# Line.net
KiCad netlist of a schematic drawn in EAGLE
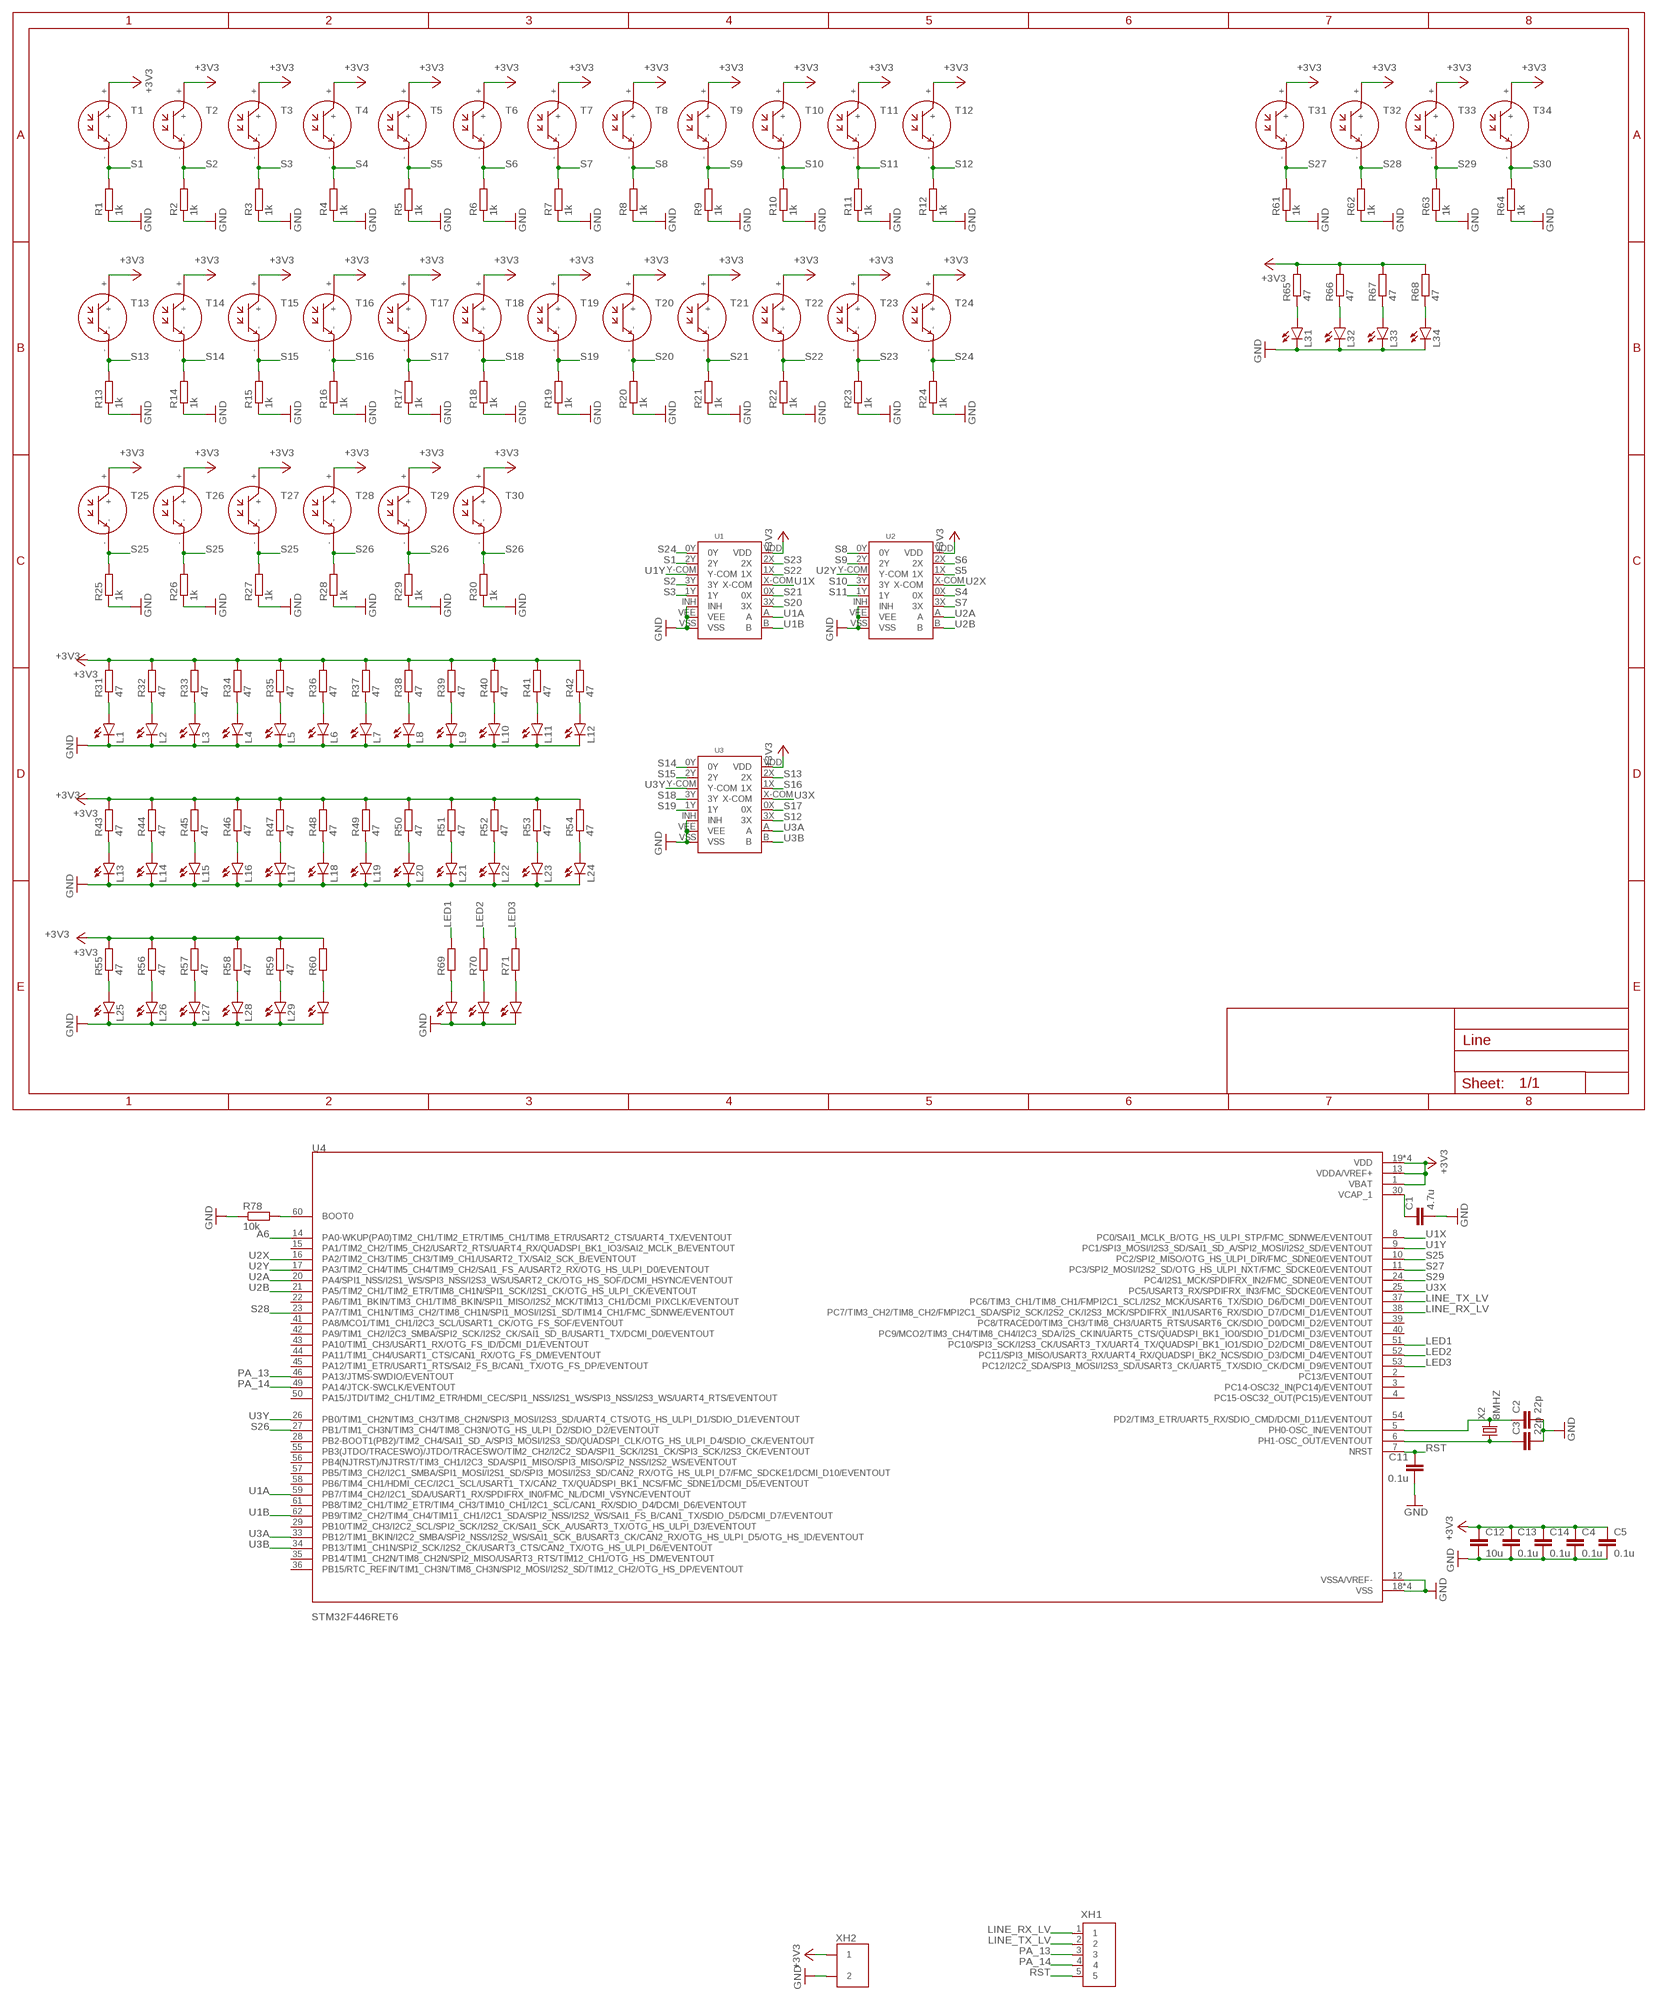
[diagram p0: schematic, sheet 1]

(export (version "E")
  (design (tool "Eeschema 10.0.6"))
  (components
    (comp (ref "C1")
      (value "4.7u")
      (footprint "eagle-import:C0603")
      (libsource (lib "eagle-import") (part "C-EUC0603"))
    )
    (comp (ref "C2")
      (value "22p")
      (footprint "eagle-import:C0603")
      (libsource (lib "eagle-import") (part "C-EUC0603"))
    )
    (comp (ref "C3")
      (value "22p")
      (footprint "eagle-import:C0603")
      (libsource (lib "eagle-import") (part "C-EUC0603"))
    )
    (comp (ref "C4")
      (value "0.1u")
      (footprint "eagle-import:C0603")
      (libsource (lib "eagle-import") (part "C-EUC0603"))
    )
    (comp (ref "C5")
      (value "0.1u")
      (footprint "eagle-import:C0603")
      (libsource (lib "eagle-import") (part "C-EUC0603"))
    )
    (comp (ref "C11")
      (value "0.1u")
      (footprint "eagle-import:C0603")
      (libsource (lib "eagle-import") (part "C-EUC0603"))
    )
    (comp (ref "C12")
      (value "10u")
      (footprint "eagle-import:C0805")
      (libsource (lib "eagle-import") (part "C-EUC0805"))
    )
    (comp (ref "C13")
      (value "0.1u")
      (footprint "eagle-import:C0603")
      (libsource (lib "eagle-import") (part "C-EUC0603"))
    )
    (comp (ref "C14")
      (value "0.1u")
      (footprint "eagle-import:C0603")
      (libsource (lib "eagle-import") (part "C-EUC0603"))
    )
    (comp (ref "L1")
      (value "SML-E12P8WT86")
      (footprint "eagle-import:LED_SML-LXFM0603SIC-TR")
      (libsource (lib "eagle-import") (part "SML-E12P8WT86"))
    )
    (comp (ref "L2")
      (value "SML-E12P8WT86")
      (footprint "eagle-import:LED_SML-LXFM0603SIC-TR")
      (libsource (lib "eagle-import") (part "SML-E12P8WT86"))
    )
    (comp (ref "L3")
      (value "SML-E12P8WT86")
      (footprint "eagle-import:LED_SML-LXFM0603SIC-TR")
      (libsource (lib "eagle-import") (part "SML-E12P8WT86"))
    )
    (comp (ref "L4")
      (value "SML-E12P8WT86")
      (footprint "eagle-import:LED_SML-LXFM0603SIC-TR")
      (libsource (lib "eagle-import") (part "SML-E12P8WT86"))
    )
    (comp (ref "L5")
      (value "SML-E12P8WT86")
      (footprint "eagle-import:LED_SML-LXFM0603SIC-TR")
      (libsource (lib "eagle-import") (part "SML-E12P8WT86"))
    )
    (comp (ref "L6")
      (value "SML-E12P8WT86")
      (footprint "eagle-import:LED_SML-LXFM0603SIC-TR")
      (libsource (lib "eagle-import") (part "SML-E12P8WT86"))
    )
    (comp (ref "L7")
      (value "SML-E12P8WT86")
      (footprint "eagle-import:LED_SML-LXFM0603SIC-TR")
      (libsource (lib "eagle-import") (part "SML-E12P8WT86"))
    )
    (comp (ref "L8")
      (value "SML-E12P8WT86")
      (footprint "eagle-import:LED_SML-LXFM0603SIC-TR")
      (libsource (lib "eagle-import") (part "SML-E12P8WT86"))
    )
    (comp (ref "L9")
      (value "SML-E12P8WT86")
      (footprint "eagle-import:LED_SML-LXFM0603SIC-TR")
      (libsource (lib "eagle-import") (part "SML-E12P8WT86"))
    )
    (comp (ref "L10")
      (value "SML-E12P8WT86")
      (footprint "eagle-import:LED_SML-LXFM0603SIC-TR")
      (libsource (lib "eagle-import") (part "SML-E12P8WT86"))
    )
    (comp (ref "L11")
      (value "SML-E12P8WT86")
      (footprint "eagle-import:LED_SML-LXFM0603SIC-TR")
      (libsource (lib "eagle-import") (part "SML-E12P8WT86"))
    )
    (comp (ref "L12")
      (value "SML-E12P8WT86")
      (footprint "eagle-import:LED_SML-LXFM0603SIC-TR")
      (libsource (lib "eagle-import") (part "SML-E12P8WT86"))
    )
    (comp (ref "L13")
      (value "SML-E12P8WT86")
      (footprint "eagle-import:LED_SML-LXFM0603SIC-TR")
      (libsource (lib "eagle-import") (part "SML-E12P8WT86"))
    )
    (comp (ref "L14")
      (value "SML-E12P8WT86")
      (footprint "eagle-import:LED_SML-LXFM0603SIC-TR")
      (libsource (lib "eagle-import") (part "SML-E12P8WT86"))
    )
    (comp (ref "L15")
      (value "SML-E12P8WT86")
      (footprint "eagle-import:LED_SML-LXFM0603SIC-TR")
      (libsource (lib "eagle-import") (part "SML-E12P8WT86"))
    )
    (comp (ref "L16")
      (value "SML-E12P8WT86")
      (footprint "eagle-import:LED_SML-LXFM0603SIC-TR")
      (libsource (lib "eagle-import") (part "SML-E12P8WT86"))
    )
    (comp (ref "L17")
      (value "SML-E12P8WT86")
      (footprint "eagle-import:LED_SML-LXFM0603SIC-TR")
      (libsource (lib "eagle-import") (part "SML-E12P8WT86"))
    )
    (comp (ref "L18")
      (value "SML-E12P8WT86")
      (footprint "eagle-import:LED_SML-LXFM0603SIC-TR")
      (libsource (lib "eagle-import") (part "SML-E12P8WT86"))
    )
    (comp (ref "L19")
      (value "SML-E12P8WT86")
      (footprint "eagle-import:LED_SML-LXFM0603SIC-TR")
      (libsource (lib "eagle-import") (part "SML-E12P8WT86"))
    )
    (comp (ref "L20")
      (value "SML-E12P8WT86")
      (footprint "eagle-import:LED_SML-LXFM0603SIC-TR")
      (libsource (lib "eagle-import") (part "SML-E12P8WT86"))
    )
    (comp (ref "L21")
      (value "SML-E12P8WT86")
      (footprint "eagle-import:LED_SML-LXFM0603SIC-TR")
      (libsource (lib "eagle-import") (part "SML-E12P8WT86"))
    )
    (comp (ref "L22")
      (value "SML-E12P8WT86")
      (footprint "eagle-import:LED_SML-LXFM0603SIC-TR")
      (libsource (lib "eagle-import") (part "SML-E12P8WT86"))
    )
    (comp (ref "L23")
      (value "SML-E12P8WT86")
      (footprint "eagle-import:LED_SML-LXFM0603SIC-TR")
      (libsource (lib "eagle-import") (part "SML-E12P8WT86"))
    )
    (comp (ref "L24")
      (value "SML-E12P8WT86")
      (footprint "eagle-import:LED_SML-LXFM0603SIC-TR")
      (libsource (lib "eagle-import") (part "SML-E12P8WT86"))
    )
    (comp (ref "L25")
      (value "SML-E12P8WT86")
      (footprint "eagle-import:LED_SML-LXFM0603SIC-TR")
      (libsource (lib "eagle-import") (part "SML-E12P8WT86"))
    )
    (comp (ref "L26")
      (value "SML-E12P8WT86")
      (footprint "eagle-import:LED_SML-LXFM0603SIC-TR")
      (libsource (lib "eagle-import") (part "SML-E12P8WT86"))
    )
    (comp (ref "L27")
      (value "SML-E12P8WT86")
      (footprint "eagle-import:LED_SML-LXFM0603SIC-TR")
      (libsource (lib "eagle-import") (part "SML-E12P8WT86"))
    )
    (comp (ref "L28")
      (value "SML-E12P8WT86")
      (footprint "eagle-import:LED_SML-LXFM0603SIC-TR")
      (libsource (lib "eagle-import") (part "SML-E12P8WT86"))
    )
    (comp (ref "L29")
      (value "SML-E12P8WT86")
      (footprint "eagle-import:LED_SML-LXFM0603SIC-TR")
      (libsource (lib "eagle-import") (part "SML-E12P8WT86"))
    )
    (comp (ref "L30")
      (value "SML-E12P8WT86")
      (footprint "eagle-import:LED_SML-LXFM0603SIC-TR")
      (libsource (lib "eagle-import") (part "SML-E12P8WT86"))
    )
    (comp (ref "L31")
      (value "SML-E12P8WT86")
      (footprint "eagle-import:LED_SML-LXFM0603SIC-TR")
      (libsource (lib "eagle-import") (part "SML-E12P8WT86"))
    )
    (comp (ref "L32")
      (value "SML-E12P8WT86")
      (footprint "eagle-import:LED_SML-LXFM0603SIC-TR")
      (libsource (lib "eagle-import") (part "SML-E12P8WT86"))
    )
    (comp (ref "L33")
      (value "SML-E12P8WT86")
      (footprint "eagle-import:LED_SML-LXFM0603SIC-TR")
      (libsource (lib "eagle-import") (part "SML-E12P8WT86"))
    )
    (comp (ref "L34")
      (value "SML-E12P8WT86")
      (footprint "eagle-import:LED_SML-LXFM0603SIC-TR")
      (libsource (lib "eagle-import") (part "SML-E12P8WT86"))
    )
    (comp (ref "L35")
      (value "SML-E12P8WT86")
      (footprint "eagle-import:LED_SML-LXFM0603SIC-TR")
      (libsource (lib "eagle-import") (part "SML-E12P8WT86"))
    )
    (comp (ref "L36")
      (value "SML-E12P8WT86")
      (footprint "eagle-import:LED_SML-LXFM0603SIC-TR")
      (libsource (lib "eagle-import") (part "SML-E12P8WT86"))
    )
    (comp (ref "L37")
      (value "SML-E12P8WT86")
      (footprint "eagle-import:LED_SML-LXFM0603SIC-TR")
      (libsource (lib "eagle-import") (part "SML-E12P8WT86"))
    )
    (comp (ref "R1")
      (value "1k")
      (footprint "eagle-import:R0603")
      (libsource (lib "eagle-import") (part "R-EU_R0603"))
    )
    (comp (ref "R2")
      (value "1k")
      (footprint "eagle-import:R0603")
      (libsource (lib "eagle-import") (part "R-EU_R0603"))
    )
    (comp (ref "R3")
      (value "1k")
      (footprint "eagle-import:R0603")
      (libsource (lib "eagle-import") (part "R-EU_R0603"))
    )
    (comp (ref "R4")
      (value "1k")
      (footprint "eagle-import:R0603")
      (libsource (lib "eagle-import") (part "R-EU_R0603"))
    )
    (comp (ref "R5")
      (value "1k")
      (footprint "eagle-import:R0603")
      (libsource (lib "eagle-import") (part "R-EU_R0603"))
    )
    (comp (ref "R6")
      (value "1k")
      (footprint "eagle-import:R0603")
      (libsource (lib "eagle-import") (part "R-EU_R0603"))
    )
    (comp (ref "R7")
      (value "1k")
      (footprint "eagle-import:R0603")
      (libsource (lib "eagle-import") (part "R-EU_R0603"))
    )
    (comp (ref "R8")
      (value "1k")
      (footprint "eagle-import:R0603")
      (libsource (lib "eagle-import") (part "R-EU_R0603"))
    )
    (comp (ref "R9")
      (value "1k")
      (footprint "eagle-import:R0603")
      (libsource (lib "eagle-import") (part "R-EU_R0603"))
    )
    (comp (ref "R10")
      (value "1k")
      (footprint "eagle-import:R0603")
      (libsource (lib "eagle-import") (part "R-EU_R0603"))
    )
    (comp (ref "R11")
      (value "1k")
      (footprint "eagle-import:R0603")
      (libsource (lib "eagle-import") (part "R-EU_R0603"))
    )
    (comp (ref "R12")
      (value "1k")
      (footprint "eagle-import:R0603")
      (libsource (lib "eagle-import") (part "R-EU_R0603"))
    )
    (comp (ref "R13")
      (value "1k")
      (footprint "eagle-import:R0603")
      (libsource (lib "eagle-import") (part "R-EU_R0603"))
    )
    (comp (ref "R14")
      (value "1k")
      (footprint "eagle-import:R0603")
      (libsource (lib "eagle-import") (part "R-EU_R0603"))
    )
    (comp (ref "R15")
      (value "1k")
      (footprint "eagle-import:R0603")
      (libsource (lib "eagle-import") (part "R-EU_R0603"))
    )
    (comp (ref "R16")
      (value "1k")
      (footprint "eagle-import:R0603")
      (libsource (lib "eagle-import") (part "R-EU_R0603"))
    )
    (comp (ref "R17")
      (value "1k")
      (footprint "eagle-import:R0603")
      (libsource (lib "eagle-import") (part "R-EU_R0603"))
    )
    (comp (ref "R18")
      (value "1k")
      (footprint "eagle-import:R0603")
      (libsource (lib "eagle-import") (part "R-EU_R0603"))
    )
    (comp (ref "R19")
      (value "1k")
      (footprint "eagle-import:R0603")
      (libsource (lib "eagle-import") (part "R-EU_R0603"))
    )
    (comp (ref "R20")
      (value "1k")
      (footprint "eagle-import:R0603")
      (libsource (lib "eagle-import") (part "R-EU_R0603"))
    )
    (comp (ref "R21")
      (value "1k")
      (footprint "eagle-import:R0603")
      (libsource (lib "eagle-import") (part "R-EU_R0603"))
    )
    (comp (ref "R22")
      (value "1k")
      (footprint "eagle-import:R0603")
      (libsource (lib "eagle-import") (part "R-EU_R0603"))
    )
    (comp (ref "R23")
      (value "1k")
      (footprint "eagle-import:R0603")
      (libsource (lib "eagle-import") (part "R-EU_R0603"))
    )
    (comp (ref "R24")
      (value "1k")
      (footprint "eagle-import:R0603")
      (libsource (lib "eagle-import") (part "R-EU_R0603"))
    )
    (comp (ref "R25")
      (value "1k")
      (footprint "eagle-import:R0603")
      (libsource (lib "eagle-import") (part "R-EU_R0603"))
    )
    (comp (ref "R26")
      (value "1k")
      (footprint "eagle-import:R0603")
      (libsource (lib "eagle-import") (part "R-EU_R0603"))
    )
    (comp (ref "R27")
      (value "1k")
      (footprint "eagle-import:R0603")
      (libsource (lib "eagle-import") (part "R-EU_R0603"))
    )
    (comp (ref "R28")
      (value "1k")
      (footprint "eagle-import:R0603")
      (libsource (lib "eagle-import") (part "R-EU_R0603"))
    )
    (comp (ref "R29")
      (value "1k")
      (footprint "eagle-import:R0603")
      (libsource (lib "eagle-import") (part "R-EU_R0603"))
    )
    (comp (ref "R30")
      (value "1k")
      (footprint "eagle-import:R0603")
      (libsource (lib "eagle-import") (part "R-EU_R0603"))
    )
    (comp (ref "R31")
      (value "47")
      (footprint "eagle-import:R0603")
      (libsource (lib "eagle-import") (part "R-EU_R0603"))
    )
    (comp (ref "R32")
      (value "47")
      (footprint "eagle-import:R0603")
      (libsource (lib "eagle-import") (part "R-EU_R0603"))
    )
    (comp (ref "R33")
      (value "47")
      (footprint "eagle-import:R0603")
      (libsource (lib "eagle-import") (part "R-EU_R0603"))
    )
    (comp (ref "R34")
      (value "47")
      (footprint "eagle-import:R0603")
      (libsource (lib "eagle-import") (part "R-EU_R0603"))
    )
    (comp (ref "R35")
      (value "47")
      (footprint "eagle-import:R0603")
      (libsource (lib "eagle-import") (part "R-EU_R0603"))
    )
    (comp (ref "R36")
      (value "47")
      (footprint "eagle-import:R0603")
      (libsource (lib "eagle-import") (part "R-EU_R0603"))
    )
    (comp (ref "R37")
      (value "47")
      (footprint "eagle-import:R0603")
      (libsource (lib "eagle-import") (part "R-EU_R0603"))
    )
    (comp (ref "R38")
      (value "47")
      (footprint "eagle-import:R0603")
      (libsource (lib "eagle-import") (part "R-EU_R0603"))
    )
    (comp (ref "R39")
      (value "47")
      (footprint "eagle-import:R0603")
      (libsource (lib "eagle-import") (part "R-EU_R0603"))
    )
    (comp (ref "R40")
      (value "47")
      (footprint "eagle-import:R0603")
      (libsource (lib "eagle-import") (part "R-EU_R0603"))
    )
    (comp (ref "R41")
      (value "47")
      (footprint "eagle-import:R0603")
      (libsource (lib "eagle-import") (part "R-EU_R0603"))
    )
    (comp (ref "R42")
      (value "47")
      (footprint "eagle-import:R0603")
      (libsource (lib "eagle-import") (part "R-EU_R0603"))
    )
    (comp (ref "R43")
      (value "47")
      (footprint "eagle-import:R0603")
      (libsource (lib "eagle-import") (part "R-EU_R0603"))
    )
    (comp (ref "R44")
      (value "47")
      (footprint "eagle-import:R0603")
      (libsource (lib "eagle-import") (part "R-EU_R0603"))
    )
    (comp (ref "R45")
      (value "47")
      (footprint "eagle-import:R0603")
      (libsource (lib "eagle-import") (part "R-EU_R0603"))
    )
    (comp (ref "R46")
      (value "47")
      (footprint "eagle-import:R0603")
      (libsource (lib "eagle-import") (part "R-EU_R0603"))
    )
    (comp (ref "R47")
      (value "47")
      (footprint "eagle-import:R0603")
      (libsource (lib "eagle-import") (part "R-EU_R0603"))
    )
    (comp (ref "R48")
      (value "47")
      (footprint "eagle-import:R0603")
      (libsource (lib "eagle-import") (part "R-EU_R0603"))
    )
    (comp (ref "R49")
      (value "47")
      (footprint "eagle-import:R0603")
      (libsource (lib "eagle-import") (part "R-EU_R0603"))
    )
    (comp (ref "R50")
      (value "47")
      (footprint "eagle-import:R0603")
      (libsource (lib "eagle-import") (part "R-EU_R0603"))
    )
    (comp (ref "R51")
      (value "47")
      (footprint "eagle-import:R0603")
      (libsource (lib "eagle-import") (part "R-EU_R0603"))
    )
    (comp (ref "R52")
      (value "47")
      (footprint "eagle-import:R0603")
      (libsource (lib "eagle-import") (part "R-EU_R0603"))
    )
    (comp (ref "R53")
      (value "47")
      (footprint "eagle-import:R0603")
      (libsource (lib "eagle-import") (part "R-EU_R0603"))
    )
    (comp (ref "R54")
      (value "47")
      (footprint "eagle-import:R0603")
      (libsource (lib "eagle-import") (part "R-EU_R0603"))
    )
    (comp (ref "R55")
      (value "47")
      (footprint "eagle-import:R0603")
      (libsource (lib "eagle-import") (part "R-EU_R0603"))
    )
    (comp (ref "R56")
      (value "47")
      (footprint "eagle-import:R0603")
      (libsource (lib "eagle-import") (part "R-EU_R0603"))
    )
    (comp (ref "R57")
      (value "47")
      (footprint "eagle-import:R0603")
      (libsource (lib "eagle-import") (part "R-EU_R0603"))
    )
    (comp (ref "R58")
      (value "47")
      (footprint "eagle-import:R0603")
      (libsource (lib "eagle-import") (part "R-EU_R0603"))
    )
    (comp (ref "R59")
      (value "47")
      (footprint "eagle-import:R0603")
      (libsource (lib "eagle-import") (part "R-EU_R0603"))
    )
    (comp (ref "R60")
      (value "47")
      (footprint "eagle-import:R0603")
      (libsource (lib "eagle-import") (part "R-EU_R0603"))
    )
    (comp (ref "R61")
      (value "1k")
      (footprint "eagle-import:R0603")
      (libsource (lib "eagle-import") (part "R-EU_R0603"))
    )
    (comp (ref "R62")
      (value "1k")
      (footprint "eagle-import:R0603")
      (libsource (lib "eagle-import") (part "R-EU_R0603"))
    )
    (comp (ref "R63")
      (value "1k")
      (footprint "eagle-import:R0603")
      (libsource (lib "eagle-import") (part "R-EU_R0603"))
    )
    (comp (ref "R64")
      (value "1k")
      (footprint "eagle-import:R0603")
      (libsource (lib "eagle-import") (part "R-EU_R0603"))
    )
    (comp (ref "R65")
      (value "47")
      (footprint "eagle-import:R0603")
      (libsource (lib "eagle-import") (part "R-EU_R0603"))
    )
    (comp (ref "R66")
      (value "47")
      (footprint "eagle-import:R0603")
      (libsource (lib "eagle-import") (part "R-EU_R0603"))
    )
    (comp (ref "R67")
      (value "47")
      (footprint "eagle-import:R0603")
      (libsource (lib "eagle-import") (part "R-EU_R0603"))
    )
    (comp (ref "R68")
      (value "47")
      (footprint "eagle-import:R0603")
      (libsource (lib "eagle-import") (part "R-EU_R0603"))
    )
    (comp (ref "R69")
      (value "150")
      (footprint "eagle-import:R0603")
      (libsource (lib "eagle-import") (part "R-EU_R0603"))
    )
    (comp (ref "R70")
      (value "150")
      (footprint "eagle-import:R0603")
      (libsource (lib "eagle-import") (part "R-EU_R0603"))
    )
    (comp (ref "R71")
      (value "150")
      (footprint "eagle-import:R0603")
      (libsource (lib "eagle-import") (part "R-EU_R0603"))
    )
    (comp (ref "R78")
      (value "10k")
      (footprint "eagle-import:R0603")
      (libsource (lib "eagle-import") (part "R-EU_R0603"))
    )
    (comp (ref "T1")
      (value "NJL7302L-F3")
      (footprint "eagle-import:NJL7302L-F3")
      (libsource (lib "eagle-import") (part "NJL7302L-F3"))
    )
    (comp (ref "T2")
      (value "NJL7302L-F3")
      (footprint "eagle-import:NJL7302L-F3")
      (libsource (lib "eagle-import") (part "NJL7302L-F3"))
    )
    (comp (ref "T3")
      (value "NJL7302L-F3")
      (footprint "eagle-import:NJL7302L-F3")
      (libsource (lib "eagle-import") (part "NJL7302L-F3"))
    )
    (comp (ref "T4")
      (value "NJL7302L-F3")
      (footprint "eagle-import:NJL7302L-F3")
      (libsource (lib "eagle-import") (part "NJL7302L-F3"))
    )
    (comp (ref "T5")
      (value "NJL7302L-F3")
      (footprint "eagle-import:NJL7302L-F3")
      (libsource (lib "eagle-import") (part "NJL7302L-F3"))
    )
    (comp (ref "T6")
      (value "NJL7302L-F3")
      (footprint "eagle-import:NJL7302L-F3")
      (libsource (lib "eagle-import") (part "NJL7302L-F3"))
    )
    (comp (ref "T7")
      (value "NJL7302L-F3")
      (footprint "eagle-import:NJL7302L-F3")
      (libsource (lib "eagle-import") (part "NJL7302L-F3"))
    )
    (comp (ref "T8")
      (value "NJL7302L-F3")
      (footprint "eagle-import:NJL7302L-F3")
      (libsource (lib "eagle-import") (part "NJL7302L-F3"))
    )
    (comp (ref "T9")
      (value "NJL7302L-F3")
      (footprint "eagle-import:NJL7302L-F3")
      (libsource (lib "eagle-import") (part "NJL7302L-F3"))
    )
    (comp (ref "T10")
      (value "NJL7302L-F3")
      (footprint "eagle-import:NJL7302L-F3")
      (libsource (lib "eagle-import") (part "NJL7302L-F3"))
    )
    (comp (ref "T11")
      (value "NJL7302L-F3")
      (footprint "eagle-import:NJL7302L-F3")
      (libsource (lib "eagle-import") (part "NJL7302L-F3"))
    )
    (comp (ref "T12")
      (value "NJL7302L-F3")
      (footprint "eagle-import:NJL7302L-F3")
      (libsource (lib "eagle-import") (part "NJL7302L-F3"))
    )
    (comp (ref "T13")
      (value "NJL7302L-F3")
      (footprint "eagle-import:NJL7302L-F3")
      (libsource (lib "eagle-import") (part "NJL7302L-F3"))
    )
    (comp (ref "T14")
      (value "NJL7302L-F3")
      (footprint "eagle-import:NJL7302L-F3")
      (libsource (lib "eagle-import") (part "NJL7302L-F3"))
    )
    (comp (ref "T15")
      (value "NJL7302L-F3")
      (footprint "eagle-import:NJL7302L-F3")
      (libsource (lib "eagle-import") (part "NJL7302L-F3"))
    )
    (comp (ref "T16")
      (value "NJL7302L-F3")
      (footprint "eagle-import:NJL7302L-F3")
      (libsource (lib "eagle-import") (part "NJL7302L-F3"))
    )
    (comp (ref "T17")
      (value "NJL7302L-F3")
      (footprint "eagle-import:NJL7302L-F3")
      (libsource (lib "eagle-import") (part "NJL7302L-F3"))
    )
    (comp (ref "T18")
      (value "NJL7302L-F3")
      (footprint "eagle-import:NJL7302L-F3")
      (libsource (lib "eagle-import") (part "NJL7302L-F3"))
    )
    (comp (ref "T19")
      (value "NJL7302L-F3")
      (footprint "eagle-import:NJL7302L-F3")
      (libsource (lib "eagle-import") (part "NJL7302L-F3"))
    )
    (comp (ref "T20")
      (value "NJL7302L-F3")
      (footprint "eagle-import:NJL7302L-F3")
      (libsource (lib "eagle-import") (part "NJL7302L-F3"))
    )
    (comp (ref "T21")
      (value "NJL7302L-F3")
      (footprint "eagle-import:NJL7302L-F3")
      (libsource (lib "eagle-import") (part "NJL7302L-F3"))
    )
    (comp (ref "T22")
      (value "NJL7302L-F3")
      (footprint "eagle-import:NJL7302L-F3")
      (libsource (lib "eagle-import") (part "NJL7302L-F3"))
    )
    (comp (ref "T23")
      (value "NJL7302L-F3")
      (footprint "eagle-import:NJL7302L-F3")
      (libsource (lib "eagle-import") (part "NJL7302L-F3"))
    )
    (comp (ref "T24")
      (value "NJL7302L-F3")
      (footprint "eagle-import:NJL7302L-F3")
      (libsource (lib "eagle-import") (part "NJL7302L-F3"))
    )
    (comp (ref "T25")
      (value "NJL7302L-F3")
      (footprint "eagle-import:NJL7302L-F3")
      (libsource (lib "eagle-import") (part "NJL7302L-F3"))
    )
    (comp (ref "T26")
      (value "NJL7302L-F3")
      (footprint "eagle-import:NJL7302L-F3")
      (libsource (lib "eagle-import") (part "NJL7302L-F3"))
    )
    (comp (ref "T27")
      (value "NJL7302L-F3")
      (footprint "eagle-import:NJL7302L-F3")
      (libsource (lib "eagle-import") (part "NJL7302L-F3"))
    )
    (comp (ref "T28")
      (value "NJL7302L-F3")
      (footprint "eagle-import:NJL7302L-F3")
      (libsource (lib "eagle-import") (part "NJL7302L-F3"))
    )
    (comp (ref "T29")
      (value "NJL7302L-F3")
      (footprint "eagle-import:NJL7302L-F3")
      (libsource (lib "eagle-import") (part "NJL7302L-F3"))
    )
    (comp (ref "T30")
      (value "NJL7302L-F3")
      (footprint "eagle-import:NJL7302L-F3")
      (libsource (lib "eagle-import") (part "NJL7302L-F3"))
    )
    (comp (ref "T31")
      (value "NJL7302L-F3")
      (footprint "eagle-import:NJL7302L-F3")
      (libsource (lib "eagle-import") (part "NJL7302L-F3"))
    )
    (comp (ref "T32")
      (value "NJL7302L-F3")
      (footprint "eagle-import:NJL7302L-F3")
      (libsource (lib "eagle-import") (part "NJL7302L-F3"))
    )
    (comp (ref "T33")
      (value "NJL7302L-F3")
      (footprint "eagle-import:NJL7302L-F3")
      (libsource (lib "eagle-import") (part "NJL7302L-F3"))
    )
    (comp (ref "T34")
      (value "NJL7302L-F3")
      (footprint "eagle-import:NJL7302L-F3")
      (libsource (lib "eagle-import") (part "NJL7302L-F3"))
    )
    (comp (ref "U1")
      (value "TC4051BP")
      (footprint "eagle-import:TC4051BP")
      (libsource (lib "eagle-import") (part "TC4051BP"))
    )
    (comp (ref "U2")
      (value "TC4051BP")
      (footprint "eagle-import:TC4051BP")
      (libsource (lib "eagle-import") (part "TC4051BP"))
    )
    (comp (ref "U3")
      (value "TC4051BP")
      (footprint "eagle-import:TC4051BP")
      (libsource (lib "eagle-import") (part "TC4051BP"))
    )
    (comp (ref "U4")
      (value "STM32F446RET6")
      (footprint "eagle-import:QFP50P1200X1200X160-64N")
      (fields (field (name "MF") "STMicroelectronics"))
      (libsource (lib "eagle-import") (part "STM32F446RET6"))
    )
    (comp (ref "X2")
      (value "8MHZ")
      (footprint "eagle-import:16MHZ")
      (libsource (lib "eagle-import") (part "16MHZ"))
    )
    (comp (ref "XH1") (value "5B") (footprint "eagle-import:5B") (libsource (lib "eagle-import") (part "5B")))
    (comp (ref "XH2") (value "2B") (footprint "eagle-import:2B") (libsource (lib "eagle-import") (part "2B")))
  )
  (nets
    (net (code "1") (name "+3V3") (class "Default")
      (node (ref "C12") (pin "1") (pinfunction "1_1") (pintype "passive"))
      (node (ref "C13") (pin "1") (pinfunction "1_1") (pintype "passive"))
      (node (ref "C14") (pin "1") (pinfunction "1_1") (pintype "passive"))
      (node (ref "C4") (pin "1") (pinfunction "1_1") (pintype "passive"))
      (node (ref "C5") (pin "1") (pinfunction "1_1") (pintype "passive"))
      (node (ref "R31") (pin "2") (pinfunction "2_2") (pintype "passive"))
      (node (ref "R32") (pin "2") (pinfunction "2_2") (pintype "passive"))
      (node (ref "R33") (pin "2") (pinfunction "2_2") (pintype "passive"))
      (node (ref "R34") (pin "2") (pinfunction "2_2") (pintype "passive"))
      (node (ref "R35") (pin "2") (pinfunction "2_2") (pintype "passive"))
      (node (ref "R36") (pin "2") (pinfunction "2_2") (pintype "passive"))
      (node (ref "R37") (pin "2") (pinfunction "2_2") (pintype "passive"))
      (node (ref "R38") (pin "2") (pinfunction "2_2") (pintype "passive"))
      (node (ref "R39") (pin "2") (pinfunction "2_2") (pintype "passive"))
      (node (ref "R40") (pin "2") (pinfunction "2_2") (pintype "passive"))
      (node (ref "R41") (pin "2") (pinfunction "2_2") (pintype "passive"))
      (node (ref "R42") (pin "2") (pinfunction "2_2") (pintype "passive"))
      (node (ref "R43") (pin "2") (pinfunction "2_2") (pintype "passive"))
      (node (ref "R44") (pin "2") (pinfunction "2_2") (pintype "passive"))
      (node (ref "R45") (pin "2") (pinfunction "2_2") (pintype "passive"))
      (node (ref "R46") (pin "2") (pinfunction "2_2") (pintype "passive"))
      (node (ref "R47") (pin "2") (pinfunction "2_2") (pintype "passive"))
      (node (ref "R48") (pin "2") (pinfunction "2_2") (pintype "passive"))
      (node (ref "R49") (pin "2") (pinfunction "2_2") (pintype "passive"))
      (node (ref "R50") (pin "2") (pinfunction "2_2") (pintype "passive"))
      (node (ref "R51") (pin "2") (pinfunction "2_2") (pintype "passive"))
      (node (ref "R52") (pin "2") (pinfunction "2_2") (pintype "passive"))
      (node (ref "R53") (pin "2") (pinfunction "2_2") (pintype "passive"))
      (node (ref "R54") (pin "2") (pinfunction "2_2") (pintype "passive"))
      (node (ref "R55") (pin "2") (pinfunction "2_2") (pintype "passive"))
      (node (ref "R56") (pin "2") (pinfunction "2_2") (pintype "passive"))
      (node (ref "R57") (pin "2") (pinfunction "2_2") (pintype "passive"))
      (node (ref "R58") (pin "2") (pinfunction "2_2") (pintype "passive"))
      (node (ref "R59") (pin "2") (pinfunction "2_2") (pintype "passive"))
      (node (ref "R60") (pin "2") (pinfunction "2_2") (pintype "passive"))
      (node (ref "R65") (pin "2") (pinfunction "2_2") (pintype "passive"))
      (node (ref "R66") (pin "2") (pinfunction "2_2") (pintype "passive"))
      (node (ref "R67") (pin "2") (pinfunction "2_2") (pintype "passive"))
      (node (ref "R68") (pin "2") (pinfunction "2_2") (pintype "passive"))
      (node (ref "T1") (pin "+") (pinfunction "+_+") (pintype "bidirectional"))
      (node (ref "T10") (pin "+") (pinfunction "+_+") (pintype "bidirectional"))
      (node (ref "T11") (pin "+") (pinfunction "+_+") (pintype "bidirectional"))
      (node (ref "T12") (pin "+") (pinfunction "+_+") (pintype "bidirectional"))
      (node (ref "T13") (pin "+") (pinfunction "+_+") (pintype "bidirectional"))
      (node (ref "T14") (pin "+") (pinfunction "+_+") (pintype "bidirectional"))
      (node (ref "T15") (pin "+") (pinfunction "+_+") (pintype "bidirectional"))
      (node (ref "T16") (pin "+") (pinfunction "+_+") (pintype "bidirectional"))
      (node (ref "T17") (pin "+") (pinfunction "+_+") (pintype "bidirectional"))
      (node (ref "T18") (pin "+") (pinfunction "+_+") (pintype "bidirectional"))
      (node (ref "T19") (pin "+") (pinfunction "+_+") (pintype "bidirectional"))
      (node (ref "T2") (pin "+") (pinfunction "+_+") (pintype "bidirectional"))
      (node (ref "T20") (pin "+") (pinfunction "+_+") (pintype "bidirectional"))
      (node (ref "T21") (pin "+") (pinfunction "+_+") (pintype "bidirectional"))
      (node (ref "T22") (pin "+") (pinfunction "+_+") (pintype "bidirectional"))
      (node (ref "T23") (pin "+") (pinfunction "+_+") (pintype "bidirectional"))
      (node (ref "T24") (pin "+") (pinfunction "+_+") (pintype "bidirectional"))
      (node (ref "T25") (pin "+") (pinfunction "+_+") (pintype "bidirectional"))
      (node (ref "T26") (pin "+") (pinfunction "+_+") (pintype "bidirectional"))
      (node (ref "T27") (pin "+") (pinfunction "+_+") (pintype "bidirectional"))
      (node (ref "T28") (pin "+") (pinfunction "+_+") (pintype "bidirectional"))
      (node (ref "T29") (pin "+") (pinfunction "+_+") (pintype "bidirectional"))
      (node (ref "T3") (pin "+") (pinfunction "+_+") (pintype "bidirectional"))
      (node (ref "T30") (pin "+") (pinfunction "+_+") (pintype "bidirectional"))
      (node (ref "T31") (pin "+") (pinfunction "+_+") (pintype "bidirectional"))
      (node (ref "T32") (pin "+") (pinfunction "+_+") (pintype "bidirectional"))
      (node (ref "T33") (pin "+") (pinfunction "+_+") (pintype "bidirectional"))
      (node (ref "T34") (pin "+") (pinfunction "+_+") (pintype "bidirectional"))
      (node (ref "T4") (pin "+") (pinfunction "+_+") (pintype "bidirectional"))
      (node (ref "T5") (pin "+") (pinfunction "+_+") (pintype "bidirectional"))
      (node (ref "T6") (pin "+") (pinfunction "+_+") (pintype "bidirectional"))
      (node (ref "T7") (pin "+") (pinfunction "+_+") (pintype "bidirectional"))
      (node (ref "T8") (pin "+") (pinfunction "+_+") (pintype "bidirectional"))
      (node (ref "T9") (pin "+") (pinfunction "+_+") (pintype "bidirectional"))
      (node (ref "U1") (pin "VDD") (pinfunction "VDD_VDD") (pintype "bidirectional"))
      (node (ref "U2") (pin "VDD") (pinfunction "VDD_VDD") (pintype "bidirectional"))
      (node (ref "U3") (pin "VDD") (pinfunction "VDD_VDD") (pintype "bidirectional"))
      (node (ref "U4") (pin "1") (pinfunction "VBAT_1") (pintype "power_in"))
      (node (ref "U4") (pin "13") (pinfunction "VDDA/VREF+_13") (pintype "power_in"))
      (node (ref "U4") (pin "19") (pinfunction "VDD_19") (pintype "power_in"))
      (node (ref "U4") (pin "32") (pinfunction "VDD_32") (pintype "power_in"))
      (node (ref "U4") (pin "48") (pinfunction "VDD_48") (pintype "power_in"))
      (node (ref "U4") (pin "64") (pinfunction "VDD_64") (pintype "power_in"))
      (node (ref "XH2") (pin "P$1") (pinfunction "1_P$1") (pintype "bidirectional"))
    )
    (net (code "2") (name "/A6") (class "Default")
      (node (ref "U4") (pin "14") (pinfunction "PA0-WKUP(PA0)TIM2_CH1/TIM2_ETR/TIM5_CH1/TIM8_ETR/USART2_CTS/UART4_TX/EVENTOUT_14") (pintype "bidirectional"))
    )
    (net (code "3") (name "/LED1") (class "Default")
      (node (ref "R69") (pin "2") (pinfunction "2_2") (pintype "passive"))
      (node (ref "U4") (pin "51") (pinfunction "PC10/SPI3_SCK/I2S3_CK/USART3_TX/UART4_TX/QUADSPI_BK1_IO1/SDIO_D2/DCMI_D8/EVENTOUT_51") (pintype "bidirectional"))
    )
    (net (code "4") (name "/LED2") (class "Default")
      (node (ref "R70") (pin "2") (pinfunction "2_2") (pintype "passive"))
      (node (ref "U4") (pin "52") (pinfunction "PC11/SPI3_MISO/USART3_RX/UART4_RX/QUADSPI_BK2_NCS/SDIO_D3/DCMI_D4/EVENTOUT_52") (pintype "bidirectional"))
    )
    (net (code "5") (name "/LED3") (class "Default")
      (node (ref "R71") (pin "2") (pinfunction "2_2") (pintype "passive"))
      (node (ref "U4") (pin "53") (pinfunction "PC12/I2C2_SDA/SPI3_MOSI/I2S3_SD/USART3_CK/UART5_TX/SDIO_CK/DCMI_D9/EVENTOUT_53") (pintype "bidirectional"))
    )
    (net (code "6") (name "/LINE_RX_LV") (class "Default")
      (node (ref "U4") (pin "38") (pinfunction "PC7/TIM3_CH2/TIM8_CH2/FMPI2C1_SDA/SPI2_SCK/I2S2_CK/I2S3_MCK/SPDIFRX_IN1/USART6_RX/SDIO_D7/DCMI_D1/EVENTOUT_38") (pintype "bidirectional"))
      (node (ref "XH1") (pin "1") (pinfunction "1_1") (pintype "bidirectional"))
    )
    (net (code "7") (name "/LINE_TX_LV") (class "Default")
      (node (ref "U4") (pin "37") (pinfunction "PC6/TIM3_CH1/TIM8_CH1/FMPI2C1_SCL/I2S2_MCK/USART6_TX/SDIO_D6/DCMI_D0/EVENTOUT_37") (pintype "bidirectional"))
      (node (ref "XH1") (pin "2") (pinfunction "2_2") (pintype "bidirectional"))
    )
    (net (code "8") (name "/PA_13") (class "Default")
      (node (ref "U4") (pin "46") (pinfunction "PA13/JTMS-SWDIO/EVENTOUT_46") (pintype "bidirectional"))
      (node (ref "XH1") (pin "3") (pinfunction "3_3") (pintype "bidirectional"))
    )
    (net (code "9") (name "/PA_14") (class "Default")
      (node (ref "U4") (pin "49") (pinfunction "PA14/JTCK-SWCLK/EVENTOUT_49") (pintype "bidirectional"))
      (node (ref "XH1") (pin "4") (pinfunction "4_4") (pintype "bidirectional"))
    )
    (net (code "10") (name "/RST") (class "Default")
      (node (ref "C11") (pin "1") (pinfunction "1_1") (pintype "passive"))
      (node (ref "U4") (pin "7") (pinfunction "NRST_7") (pintype "bidirectional"))
      (node (ref "XH1") (pin "5") (pinfunction "5_5") (pintype "bidirectional"))
    )
    (net (code "11") (name "/S1") (class "Default")
      (node (ref "R1") (pin "2") (pinfunction "2_2") (pintype "passive"))
      (node (ref "T1") (pin "-") (pinfunction "-_-") (pintype "bidirectional"))
      (node (ref "U1") (pin "2Y") (pinfunction "2Y_2Y") (pintype "bidirectional"))
    )
    (net (code "12") (name "/S2") (class "Default")
      (node (ref "R2") (pin "2") (pinfunction "2_2") (pintype "passive"))
      (node (ref "T2") (pin "-") (pinfunction "-_-") (pintype "bidirectional"))
      (node (ref "U1") (pin "3Y") (pinfunction "3Y_3Y") (pintype "bidirectional"))
    )
    (net (code "13") (name "/S3") (class "Default")
      (node (ref "R3") (pin "2") (pinfunction "2_2") (pintype "passive"))
      (node (ref "T3") (pin "-") (pinfunction "-_-") (pintype "bidirectional"))
      (node (ref "U1") (pin "1Y") (pinfunction "1Y_1Y") (pintype "bidirectional"))
    )
    (net (code "14") (name "/S4") (class "Default")
      (node (ref "R4") (pin "2") (pinfunction "2_2") (pintype "passive"))
      (node (ref "T4") (pin "-") (pinfunction "-_-") (pintype "bidirectional"))
      (node (ref "U2") (pin "0X") (pinfunction "0X_0X") (pintype "bidirectional"))
    )
    (net (code "15") (name "/S5") (class "Default")
      (node (ref "R5") (pin "2") (pinfunction "2_2") (pintype "passive"))
      (node (ref "T5") (pin "-") (pinfunction "-_-") (pintype "bidirectional"))
      (node (ref "U2") (pin "1X") (pinfunction "1X_1X") (pintype "bidirectional"))
    )
    (net (code "16") (name "/S6") (class "Default")
      (node (ref "R6") (pin "2") (pinfunction "2_2") (pintype "passive"))
      (node (ref "T6") (pin "-") (pinfunction "-_-") (pintype "bidirectional"))
      (node (ref "U2") (pin "2X") (pinfunction "2X_2X") (pintype "bidirectional"))
    )
    (net (code "17") (name "/S7") (class "Default")
      (node (ref "R7") (pin "2") (pinfunction "2_2") (pintype "passive"))
      (node (ref "T7") (pin "-") (pinfunction "-_-") (pintype "bidirectional"))
      (node (ref "U2") (pin "3X") (pinfunction "3X_3X") (pintype "bidirectional"))
    )
    (net (code "18") (name "/S8") (class "Default")
      (node (ref "R8") (pin "2") (pinfunction "2_2") (pintype "passive"))
      (node (ref "T8") (pin "-") (pinfunction "-_-") (pintype "bidirectional"))
      (node (ref "U2") (pin "0Y") (pinfunction "0Y_0Y") (pintype "bidirectional"))
    )
    (net (code "19") (name "/S9") (class "Default")
      (node (ref "R9") (pin "2") (pinfunction "2_2") (pintype "passive"))
      (node (ref "T9") (pin "-") (pinfunction "-_-") (pintype "bidirectional"))
      (node (ref "U2") (pin "2Y") (pinfunction "2Y_2Y") (pintype "bidirectional"))
    )
    (net (code "20") (name "/S10") (class "Default")
      (node (ref "R10") (pin "2") (pinfunction "2_2") (pintype "passive"))
      (node (ref "T10") (pin "-") (pinfunction "-_-") (pintype "bidirectional"))
      (node (ref "U2") (pin "3Y") (pinfunction "3Y_3Y") (pintype "bidirectional"))
    )
    (net (code "21") (name "/S11") (class "Default")
      (node (ref "R11") (pin "2") (pinfunction "2_2") (pintype "passive"))
      (node (ref "T11") (pin "-") (pinfunction "-_-") (pintype "bidirectional"))
      (node (ref "U2") (pin "1Y") (pinfunction "1Y_1Y") (pintype "bidirectional"))
    )
    (net (code "22") (name "/S12") (class "Default")
      (node (ref "R12") (pin "2") (pinfunction "2_2") (pintype "passive"))
      (node (ref "T12") (pin "-") (pinfunction "-_-") (pintype "bidirectional"))
      (node (ref "U3") (pin "3X") (pinfunction "3X_3X") (pintype "bidirectional"))
    )
    (net (code "23") (name "/S13") (class "Default")
      (node (ref "R13") (pin "2") (pinfunction "2_2") (pintype "passive"))
      (node (ref "T13") (pin "-") (pinfunction "-_-") (pintype "bidirectional"))
      (node (ref "U3") (pin "2X") (pinfunction "2X_2X") (pintype "bidirectional"))
    )
    (net (code "24") (name "/S14") (class "Default")
      (node (ref "R14") (pin "2") (pinfunction "2_2") (pintype "passive"))
      (node (ref "T14") (pin "-") (pinfunction "-_-") (pintype "bidirectional"))
      (node (ref "U3") (pin "0Y") (pinfunction "0Y_0Y") (pintype "bidirectional"))
    )
    (net (code "25") (name "/S15") (class "Default")
      (node (ref "R15") (pin "2") (pinfunction "2_2") (pintype "passive"))
      (node (ref "T15") (pin "-") (pinfunction "-_-") (pintype "bidirectional"))
      (node (ref "U3") (pin "2Y") (pinfunction "2Y_2Y") (pintype "bidirectional"))
    )
    (net (code "26") (name "/S16") (class "Default")
      (node (ref "R16") (pin "2") (pinfunction "2_2") (pintype "passive"))
      (node (ref "T16") (pin "-") (pinfunction "-_-") (pintype "bidirectional"))
      (node (ref "U3") (pin "1X") (pinfunction "1X_1X") (pintype "bidirectional"))
    )
    (net (code "27") (name "/S17") (class "Default")
      (node (ref "R17") (pin "2") (pinfunction "2_2") (pintype "passive"))
      (node (ref "T17") (pin "-") (pinfunction "-_-") (pintype "bidirectional"))
      (node (ref "U3") (pin "0X") (pinfunction "0X_0X") (pintype "bidirectional"))
    )
    (net (code "28") (name "/S18") (class "Default")
      (node (ref "R18") (pin "2") (pinfunction "2_2") (pintype "passive"))
      (node (ref "T18") (pin "-") (pinfunction "-_-") (pintype "bidirectional"))
      (node (ref "U3") (pin "3Y") (pinfunction "3Y_3Y") (pintype "bidirectional"))
    )
    (net (code "29") (name "/S19") (class "Default")
      (node (ref "R19") (pin "2") (pinfunction "2_2") (pintype "passive"))
      (node (ref "T19") (pin "-") (pinfunction "-_-") (pintype "bidirectional"))
      (node (ref "U3") (pin "1Y") (pinfunction "1Y_1Y") (pintype "bidirectional"))
    )
    (net (code "30") (name "/S20") (class "Default")
      (node (ref "R20") (pin "2") (pinfunction "2_2") (pintype "passive"))
      (node (ref "T20") (pin "-") (pinfunction "-_-") (pintype "bidirectional"))
      (node (ref "U1") (pin "3X") (pinfunction "3X_3X") (pintype "bidirectional"))
    )
    (net (code "31") (name "/S21") (class "Default")
      (node (ref "R21") (pin "2") (pinfunction "2_2") (pintype "passive"))
      (node (ref "T21") (pin "-") (pinfunction "-_-") (pintype "bidirectional"))
      (node (ref "U1") (pin "0X") (pinfunction "0X_0X") (pintype "bidirectional"))
    )
    (net (code "32") (name "/S22") (class "Default")
      (node (ref "R22") (pin "2") (pinfunction "2_2") (pintype "passive"))
      (node (ref "T22") (pin "-") (pinfunction "-_-") (pintype "bidirectional"))
      (node (ref "U1") (pin "1X") (pinfunction "1X_1X") (pintype "bidirectional"))
    )
    (net (code "33") (name "/S23") (class "Default")
      (node (ref "R23") (pin "2") (pinfunction "2_2") (pintype "passive"))
      (node (ref "T23") (pin "-") (pinfunction "-_-") (pintype "bidirectional"))
      (node (ref "U1") (pin "2X") (pinfunction "2X_2X") (pintype "bidirectional"))
    )
    (net (code "34") (name "/S24") (class "Default")
      (node (ref "R24") (pin "2") (pinfunction "2_2") (pintype "passive"))
      (node (ref "T24") (pin "-") (pinfunction "-_-") (pintype "bidirectional"))
      (node (ref "U1") (pin "0Y") (pinfunction "0Y_0Y") (pintype "bidirectional"))
    )
    (net (code "35") (name "/S25") (class "Default")
      (node (ref "R25") (pin "2") (pinfunction "2_2") (pintype "passive"))
      (node (ref "R26") (pin "2") (pinfunction "2_2") (pintype "passive"))
      (node (ref "R27") (pin "2") (pinfunction "2_2") (pintype "passive"))
      (node (ref "T25") (pin "-") (pinfunction "-_-") (pintype "bidirectional"))
      (node (ref "T26") (pin "-") (pinfunction "-_-") (pintype "bidirectional"))
      (node (ref "T27") (pin "-") (pinfunction "-_-") (pintype "bidirectional"))
      (node (ref "U4") (pin "10") (pinfunction "PC2/SPI2_MISO/OTG_HS_ULPI_DIR/FMC_SDNE0/EVENTOUT_10") (pintype "bidirectional"))
    )
    (net (code "36") (name "/S26") (class "Default")
      (node (ref "R28") (pin "2") (pinfunction "2_2") (pintype "passive"))
      (node (ref "R29") (pin "2") (pinfunction "2_2") (pintype "passive"))
      (node (ref "R30") (pin "2") (pinfunction "2_2") (pintype "passive"))
      (node (ref "T28") (pin "-") (pinfunction "-_-") (pintype "bidirectional"))
      (node (ref "T29") (pin "-") (pinfunction "-_-") (pintype "bidirectional"))
      (node (ref "T30") (pin "-") (pinfunction "-_-") (pintype "bidirectional"))
      (node (ref "U4") (pin "27") (pinfunction "PB1/TIM1_CH3N/TIM3_CH4/TIM8_CH3N/OTG_HS_ULPI_D2/SDIO_D2/EVENTOUT_27") (pintype "bidirectional"))
    )
    (net (code "37") (name "/S27") (class "Default")
      (node (ref "R61") (pin "2") (pinfunction "2_2") (pintype "passive"))
      (node (ref "T31") (pin "-") (pinfunction "-_-") (pintype "bidirectional"))
      (node (ref "U4") (pin "11") (pinfunction "PC3/SPI2_MOSI/I2S2_SD/OTG_HS_ULPI_NXT/FMC_SDCKE0/EVENTOUT_11") (pintype "bidirectional"))
    )
    (net (code "38") (name "/S28") (class "Default")
      (node (ref "R62") (pin "2") (pinfunction "2_2") (pintype "passive"))
      (node (ref "T32") (pin "-") (pinfunction "-_-") (pintype "bidirectional"))
      (node (ref "U4") (pin "23") (pinfunction "PA7/TIM1_CH1N/TIM3_CH2/TIM8_CH1N/SPI1_MOSI/I2S1_SD/TIM14_CH1/FMC_SDNWE/EVENTOUT_23") (pintype "bidirectional"))
    )
    (net (code "39") (name "/S29") (class "Default")
      (node (ref "R63") (pin "2") (pinfunction "2_2") (pintype "passive"))
      (node (ref "T33") (pin "-") (pinfunction "-_-") (pintype "bidirectional"))
      (node (ref "U4") (pin "24") (pinfunction "PC4/I2S1_MCK/SPDIFRX_IN2/FMC_SDNE0/EVENTOUT_24") (pintype "bidirectional"))
    )
    (net (code "40") (name "/S30") (class "Default")
      (node (ref "R64") (pin "2") (pinfunction "2_2") (pintype "passive"))
      (node (ref "T34") (pin "-") (pinfunction "-_-") (pintype "bidirectional"))
    )
    (net (code "41") (name "/U1A") (class "Default")
      (node (ref "U1") (pin "A") (pinfunction "A_A") (pintype "bidirectional"))
      (node (ref "U4") (pin "59") (pinfunction "PB7/TIM4_CH2/I2C1_SDA/USART1_RX/SPDIFRX_IN0/FMC_NL/DCMI_VSYNC/EVENTOUT_59") (pintype "bidirectional"))
    )
    (net (code "42") (name "/U1B") (class "Default")
      (node (ref "U1") (pin "B") (pinfunction "B_B") (pintype "bidirectional"))
      (node (ref "U4") (pin "62") (pinfunction "PB9/TIM2_CH2/TIM4_CH4/TIM11_CH1/I2C1_SDA/SPI2_NSS/I2S2_WS/SAI1_FS_B/CAN1_TX/SDIO_D5/DCMI_D7/EVENTOUT_62") (pintype "bidirectional"))
    )
    (net (code "43") (name "/U1X") (class "Default")
      (node (ref "U1") (pin "X-COM") (pinfunction "X-COM_X-COM") (pintype "bidirectional"))
      (node (ref "U4") (pin "8") (pinfunction "PC0/SAI1_MCLK_B/OTG_HS_ULPI_STP/FMC_SDNWE/EVENTOUT_8") (pintype "bidirectional"))
    )
    (net (code "44") (name "/U1Y") (class "Default")
      (node (ref "U1") (pin "Y-COM") (pinfunction "Y-COM_Y-COM") (pintype "bidirectional"))
      (node (ref "U4") (pin "9") (pinfunction "PC1/SPI3_MOSI/I2S3_SD/SAI1_SD_A/SPI2_MOSI/I2S2_SD/EVENTOUT_9") (pintype "bidirectional"))
    )
    (net (code "45") (name "/U2A") (class "Default")
      (node (ref "U2") (pin "A") (pinfunction "A_A") (pintype "bidirectional"))
      (node (ref "U4") (pin "20") (pinfunction "PA4/SPI1_NSS/I2S1_WS/SPI3_NSS/I2S3_WS/USART2_CK/OTG_HS_SOF/DCMI_HSYNC/EVENTOUT_20") (pintype "bidirectional"))
    )
    (net (code "46") (name "/U2B") (class "Default")
      (node (ref "U2") (pin "B") (pinfunction "B_B") (pintype "bidirectional"))
      (node (ref "U4") (pin "21") (pinfunction "PA5/TIM2_CH1/TIM2_ETR/TIM8_CH1N/SPI1_SCK/I2S1_CK/OTG_HS_ULPI_CK/EVENTOUT_21") (pintype "bidirectional"))
    )
    (net (code "47") (name "/U2X") (class "Default")
      (node (ref "U2") (pin "X-COM") (pinfunction "X-COM_X-COM") (pintype "bidirectional"))
      (node (ref "U4") (pin "16") (pinfunction "PA2/TIM2_CH3/TIM5_CH3/TIM9_CH1/USART2_TX/SAI2_SCK_B/EVENTOUT_16") (pintype "bidirectional"))
    )
    (net (code "48") (name "/U2Y") (class "Default")
      (node (ref "U2") (pin "Y-COM") (pinfunction "Y-COM_Y-COM") (pintype "bidirectional"))
      (node (ref "U4") (pin "17") (pinfunction "PA3/TIM2_CH4/TIM5_CH4/TIM9_CH2/SAI1_FS_A/USART2_RX/OTG_HS_ULPI_D0/EVENTOUT_17") (pintype "bidirectional"))
    )
    (net (code "49") (name "/U3A") (class "Default")
      (node (ref "U3") (pin "A") (pinfunction "A_A") (pintype "bidirectional"))
      (node (ref "U4") (pin "33") (pinfunction "PB12/TIM1_BKIN/I2C2_SMBA/SPI2_NSS/I2S2_WS/SAI1_SCK_B/USART3_CK/CAN2_RX/OTG_HS_ULPI_D5/OTG_HS_ID/EVENTOUT_33") (pintype "bidirectional"))
    )
    (net (code "50") (name "/U3B") (class "Default")
      (node (ref "U3") (pin "B") (pinfunction "B_B") (pintype "bidirectional"))
      (node (ref "U4") (pin "34") (pinfunction "PB13/TIM1_CH1N/SPI2_SCK/I2S2_CK/USART3_CTS/CAN2_TX/OTG_HS_ULPI_D6/EVENTOUT_34") (pintype "bidirectional"))
    )
    (net (code "51") (name "/U3X") (class "Default")
      (node (ref "U3") (pin "X-COM") (pinfunction "X-COM_X-COM") (pintype "bidirectional"))
      (node (ref "U4") (pin "25") (pinfunction "PC5/USART3_RX/SPDIFRX_IN3/FMC_SDCKE0/EVENTOUT_25") (pintype "bidirectional"))
    )
    (net (code "52") (name "/U3Y") (class "Default")
      (node (ref "U3") (pin "Y-COM") (pinfunction "Y-COM_Y-COM") (pintype "bidirectional"))
      (node (ref "U4") (pin "26") (pinfunction "PB0/TIM1_CH2N/TIM3_CH3/TIM8_CH2N/SPI3_MOSI/I2S3_SD/UART4_CTS/OTG_HS_ULPI_D1/SDIO_D1/EVENTOUT_26") (pintype "bidirectional"))
    )
    (net (code "53") (name "GND") (class "Default")
      (node (ref "C1") (pin "2") (pinfunction "2_2") (pintype "passive"))
      (node (ref "C11") (pin "2") (pinfunction "2_2") (pintype "passive"))
      (node (ref "C12") (pin "2") (pinfunction "2_2") (pintype "passive"))
      (node (ref "C13") (pin "2") (pinfunction "2_2") (pintype "passive"))
      (node (ref "C14") (pin "2") (pinfunction "2_2") (pintype "passive"))
      (node (ref "C2") (pin "2") (pinfunction "2_2") (pintype "passive"))
      (node (ref "C3") (pin "2") (pinfunction "2_2") (pintype "passive"))
      (node (ref "C4") (pin "2") (pinfunction "2_2") (pintype "passive"))
      (node (ref "C5") (pin "2") (pinfunction "2_2") (pintype "passive"))
      (node (ref "L1") (pin "C") (pinfunction "C_C") (pintype "passive"))
      (node (ref "L10") (pin "C") (pinfunction "C_C") (pintype "passive"))
      (node (ref "L11") (pin "C") (pinfunction "C_C") (pintype "passive"))
      (node (ref "L12") (pin "C") (pinfunction "C_C") (pintype "passive"))
      (node (ref "L13") (pin "C") (pinfunction "C_C") (pintype "passive"))
      (node (ref "L14") (pin "C") (pinfunction "C_C") (pintype "passive"))
      (node (ref "L15") (pin "C") (pinfunction "C_C") (pintype "passive"))
      (node (ref "L16") (pin "C") (pinfunction "C_C") (pintype "passive"))
      (node (ref "L17") (pin "C") (pinfunction "C_C") (pintype "passive"))
      (node (ref "L18") (pin "C") (pinfunction "C_C") (pintype "passive"))
      (node (ref "L19") (pin "C") (pinfunction "C_C") (pintype "passive"))
      (node (ref "L2") (pin "C") (pinfunction "C_C") (pintype "passive"))
      (node (ref "L20") (pin "C") (pinfunction "C_C") (pintype "passive"))
      (node (ref "L21") (pin "C") (pinfunction "C_C") (pintype "passive"))
      (node (ref "L22") (pin "C") (pinfunction "C_C") (pintype "passive"))
      (node (ref "L23") (pin "C") (pinfunction "C_C") (pintype "passive"))
      (node (ref "L24") (pin "C") (pinfunction "C_C") (pintype "passive"))
      (node (ref "L25") (pin "C") (pinfunction "C_C") (pintype "passive"))
      (node (ref "L26") (pin "C") (pinfunction "C_C") (pintype "passive"))
      (node (ref "L27") (pin "C") (pinfunction "C_C") (pintype "passive"))
      (node (ref "L28") (pin "C") (pinfunction "C_C") (pintype "passive"))
      (node (ref "L29") (pin "C") (pinfunction "C_C") (pintype "passive"))
      (node (ref "L3") (pin "C") (pinfunction "C_C") (pintype "passive"))
      (node (ref "L30") (pin "C") (pinfunction "C_C") (pintype "passive"))
      (node (ref "L31") (pin "C") (pinfunction "C_C") (pintype "passive"))
      (node (ref "L32") (pin "C") (pinfunction "C_C") (pintype "passive"))
      (node (ref "L33") (pin "C") (pinfunction "C_C") (pintype "passive"))
      (node (ref "L34") (pin "C") (pinfunction "C_C") (pintype "passive"))
      (node (ref "L35") (pin "C") (pinfunction "C_C") (pintype "passive"))
      (node (ref "L36") (pin "C") (pinfunction "C_C") (pintype "passive"))
      (node (ref "L37") (pin "C") (pinfunction "C_C") (pintype "passive"))
      (node (ref "L4") (pin "C") (pinfunction "C_C") (pintype "passive"))
      (node (ref "L5") (pin "C") (pinfunction "C_C") (pintype "passive"))
      (node (ref "L6") (pin "C") (pinfunction "C_C") (pintype "passive"))
      (node (ref "L7") (pin "C") (pinfunction "C_C") (pintype "passive"))
      (node (ref "L8") (pin "C") (pinfunction "C_C") (pintype "passive"))
      (node (ref "L9") (pin "C") (pinfunction "C_C") (pintype "passive"))
      (node (ref "R1") (pin "1") (pinfunction "1_1") (pintype "passive"))
      (node (ref "R10") (pin "1") (pinfunction "1_1") (pintype "passive"))
      (node (ref "R11") (pin "1") (pinfunction "1_1") (pintype "passive"))
      (node (ref "R12") (pin "1") (pinfunction "1_1") (pintype "passive"))
      (node (ref "R13") (pin "1") (pinfunction "1_1") (pintype "passive"))
      (node (ref "R14") (pin "1") (pinfunction "1_1") (pintype "passive"))
      (node (ref "R15") (pin "1") (pinfunction "1_1") (pintype "passive"))
      (node (ref "R16") (pin "1") (pinfunction "1_1") (pintype "passive"))
      (node (ref "R17") (pin "1") (pinfunction "1_1") (pintype "passive"))
      (node (ref "R18") (pin "1") (pinfunction "1_1") (pintype "passive"))
      (node (ref "R19") (pin "1") (pinfunction "1_1") (pintype "passive"))
      (node (ref "R2") (pin "1") (pinfunction "1_1") (pintype "passive"))
      (node (ref "R20") (pin "1") (pinfunction "1_1") (pintype "passive"))
      (node (ref "R21") (pin "1") (pinfunction "1_1") (pintype "passive"))
      (node (ref "R22") (pin "1") (pinfunction "1_1") (pintype "passive"))
      (node (ref "R23") (pin "1") (pinfunction "1_1") (pintype "passive"))
      (node (ref "R24") (pin "1") (pinfunction "1_1") (pintype "passive"))
      (node (ref "R25") (pin "1") (pinfunction "1_1") (pintype "passive"))
      (node (ref "R26") (pin "1") (pinfunction "1_1") (pintype "passive"))
      (node (ref "R27") (pin "1") (pinfunction "1_1") (pintype "passive"))
      (node (ref "R28") (pin "1") (pinfunction "1_1") (pintype "passive"))
      (node (ref "R29") (pin "1") (pinfunction "1_1") (pintype "passive"))
      (node (ref "R3") (pin "1") (pinfunction "1_1") (pintype "passive"))
      (node (ref "R30") (pin "1") (pinfunction "1_1") (pintype "passive"))
      (node (ref "R4") (pin "1") (pinfunction "1_1") (pintype "passive"))
      (node (ref "R5") (pin "1") (pinfunction "1_1") (pintype "passive"))
      (node (ref "R6") (pin "1") (pinfunction "1_1") (pintype "passive"))
      (node (ref "R61") (pin "1") (pinfunction "1_1") (pintype "passive"))
      (node (ref "R62") (pin "1") (pinfunction "1_1") (pintype "passive"))
      (node (ref "R63") (pin "1") (pinfunction "1_1") (pintype "passive"))
      (node (ref "R64") (pin "1") (pinfunction "1_1") (pintype "passive"))
      (node (ref "R7") (pin "1") (pinfunction "1_1") (pintype "passive"))
      (node (ref "R78") (pin "1") (pinfunction "1_1") (pintype "passive"))
      (node (ref "R8") (pin "1") (pinfunction "1_1") (pintype "passive"))
      (node (ref "R9") (pin "1") (pinfunction "1_1") (pintype "passive"))
      (node (ref "U1") (pin "INH") (pinfunction "INH_INH") (pintype "bidirectional"))
      (node (ref "U1") (pin "VEE") (pinfunction "VEE_VEE") (pintype "bidirectional"))
      (node (ref "U1") (pin "VSS") (pinfunction "VSS_VSS") (pintype "bidirectional"))
      (node (ref "U2") (pin "INH") (pinfunction "INH_INH") (pintype "bidirectional"))
      (node (ref "U2") (pin "VEE") (pinfunction "VEE_VEE") (pintype "bidirectional"))
      (node (ref "U2") (pin "VSS") (pinfunction "VSS_VSS") (pintype "bidirectional"))
      (node (ref "U3") (pin "INH") (pinfunction "INH_INH") (pintype "bidirectional"))
      (node (ref "U3") (pin "VEE") (pinfunction "VEE_VEE") (pintype "bidirectional"))
      (node (ref "U3") (pin "VSS") (pinfunction "VSS_VSS") (pintype "bidirectional"))
      (node (ref "U4") (pin "12") (pinfunction "VSSA/VREF-_12") (pintype "power_in"))
      (node (ref "U4") (pin "18") (pinfunction "VSS_18") (pintype "power_in"))
      (node (ref "U4") (pin "31") (pinfunction "VSS_31") (pintype "power_in"))
      (node (ref "U4") (pin "47") (pinfunction "VSS_47") (pintype "power_in"))
      (node (ref "U4") (pin "63") (pinfunction "VSS_63") (pintype "power_in"))
      (node (ref "XH2") (pin "P$2") (pinfunction "2_P$2") (pintype "bidirectional"))
    )
    (net (code "54") (name "Net-(L1-PadA)") (class "Default")
      (node (ref "L1") (pin "A") (pinfunction "A_A") (pintype "passive"))
      (node (ref "R31") (pin "1") (pinfunction "1_1") (pintype "passive"))
    )
    (net (code "55") (name "Net-(L2-PadA)") (class "Default")
      (node (ref "L2") (pin "A") (pinfunction "A_A") (pintype "passive"))
      (node (ref "R32") (pin "1") (pinfunction "1_1") (pintype "passive"))
    )
    (net (code "56") (name "Net-(L3-PadA)") (class "Default")
      (node (ref "L3") (pin "A") (pinfunction "A_A") (pintype "passive"))
      (node (ref "R33") (pin "1") (pinfunction "1_1") (pintype "passive"))
    )
    (net (code "57") (name "Net-(L4-PadA)") (class "Default")
      (node (ref "L4") (pin "A") (pinfunction "A_A") (pintype "passive"))
      (node (ref "R34") (pin "1") (pinfunction "1_1") (pintype "passive"))
    )
    (net (code "58") (name "Net-(L5-PadA)") (class "Default")
      (node (ref "L5") (pin "A") (pinfunction "A_A") (pintype "passive"))
      (node (ref "R35") (pin "1") (pinfunction "1_1") (pintype "passive"))
    )
    (net (code "59") (name "Net-(L6-PadA)") (class "Default")
      (node (ref "L6") (pin "A") (pinfunction "A_A") (pintype "passive"))
      (node (ref "R36") (pin "1") (pinfunction "1_1") (pintype "passive"))
    )
    (net (code "60") (name "Net-(L7-PadA)") (class "Default")
      (node (ref "L7") (pin "A") (pinfunction "A_A") (pintype "passive"))
      (node (ref "R37") (pin "1") (pinfunction "1_1") (pintype "passive"))
    )
    (net (code "61") (name "Net-(L8-PadA)") (class "Default")
      (node (ref "L8") (pin "A") (pinfunction "A_A") (pintype "passive"))
      (node (ref "R38") (pin "1") (pinfunction "1_1") (pintype "passive"))
    )
    (net (code "62") (name "Net-(L9-PadA)") (class "Default")
      (node (ref "L9") (pin "A") (pinfunction "A_A") (pintype "passive"))
      (node (ref "R39") (pin "1") (pinfunction "1_1") (pintype "passive"))
    )
    (net (code "63") (name "Net-(L10-PadA)") (class "Default")
      (node (ref "L10") (pin "A") (pinfunction "A_A") (pintype "passive"))
      (node (ref "R40") (pin "1") (pinfunction "1_1") (pintype "passive"))
    )
    (net (code "64") (name "Net-(L11-PadA)") (class "Default")
      (node (ref "L11") (pin "A") (pinfunction "A_A") (pintype "passive"))
      (node (ref "R41") (pin "1") (pinfunction "1_1") (pintype "passive"))
    )
    (net (code "65") (name "Net-(L12-PadA)") (class "Default")
      (node (ref "L12") (pin "A") (pinfunction "A_A") (pintype "passive"))
      (node (ref "R42") (pin "1") (pinfunction "1_1") (pintype "passive"))
    )
    (net (code "66") (name "Net-(L13-PadA)") (class "Default")
      (node (ref "L13") (pin "A") (pinfunction "A_A") (pintype "passive"))
      (node (ref "R43") (pin "1") (pinfunction "1_1") (pintype "passive"))
    )
    (net (code "67") (name "Net-(L14-PadA)") (class "Default")
      (node (ref "L14") (pin "A") (pinfunction "A_A") (pintype "passive"))
      (node (ref "R44") (pin "1") (pinfunction "1_1") (pintype "passive"))
    )
    (net (code "68") (name "Net-(L15-PadA)") (class "Default")
      (node (ref "L15") (pin "A") (pinfunction "A_A") (pintype "passive"))
      (node (ref "R45") (pin "1") (pinfunction "1_1") (pintype "passive"))
    )
    (net (code "69") (name "Net-(L16-PadA)") (class "Default")
      (node (ref "L16") (pin "A") (pinfunction "A_A") (pintype "passive"))
      (node (ref "R46") (pin "1") (pinfunction "1_1") (pintype "passive"))
    )
    (net (code "70") (name "Net-(L17-PadA)") (class "Default")
      (node (ref "L17") (pin "A") (pinfunction "A_A") (pintype "passive"))
      (node (ref "R47") (pin "1") (pinfunction "1_1") (pintype "passive"))
    )
    (net (code "71") (name "Net-(L18-PadA)") (class "Default")
      (node (ref "L18") (pin "A") (pinfunction "A_A") (pintype "passive"))
      (node (ref "R48") (pin "1") (pinfunction "1_1") (pintype "passive"))
    )
    (net (code "72") (name "Net-(L19-PadA)") (class "Default")
      (node (ref "L19") (pin "A") (pinfunction "A_A") (pintype "passive"))
      (node (ref "R49") (pin "1") (pinfunction "1_1") (pintype "passive"))
    )
    (net (code "73") (name "Net-(L20-PadA)") (class "Default")
      (node (ref "L20") (pin "A") (pinfunction "A_A") (pintype "passive"))
      (node (ref "R50") (pin "1") (pinfunction "1_1") (pintype "passive"))
    )
    (net (code "74") (name "Net-(L21-PadA)") (class "Default")
      (node (ref "L21") (pin "A") (pinfunction "A_A") (pintype "passive"))
      (node (ref "R51") (pin "1") (pinfunction "1_1") (pintype "passive"))
    )
    (net (code "75") (name "Net-(L22-PadA)") (class "Default")
      (node (ref "L22") (pin "A") (pinfunction "A_A") (pintype "passive"))
      (node (ref "R52") (pin "1") (pinfunction "1_1") (pintype "passive"))
    )
    (net (code "76") (name "Net-(L23-PadA)") (class "Default")
      (node (ref "L23") (pin "A") (pinfunction "A_A") (pintype "passive"))
      (node (ref "R53") (pin "1") (pinfunction "1_1") (pintype "passive"))
    )
    (net (code "77") (name "Net-(L24-PadA)") (class "Default")
      (node (ref "L24") (pin "A") (pinfunction "A_A") (pintype "passive"))
      (node (ref "R54") (pin "1") (pinfunction "1_1") (pintype "passive"))
    )
    (net (code "78") (name "Net-(L25-PadA)") (class "Default")
      (node (ref "L25") (pin "A") (pinfunction "A_A") (pintype "passive"))
      (node (ref "R55") (pin "1") (pinfunction "1_1") (pintype "passive"))
    )
    (net (code "79") (name "Net-(L26-PadA)") (class "Default")
      (node (ref "L26") (pin "A") (pinfunction "A_A") (pintype "passive"))
      (node (ref "R56") (pin "1") (pinfunction "1_1") (pintype "passive"))
    )
    (net (code "80") (name "Net-(L27-PadA)") (class "Default")
      (node (ref "L27") (pin "A") (pinfunction "A_A") (pintype "passive"))
      (node (ref "R57") (pin "1") (pinfunction "1_1") (pintype "passive"))
    )
    (net (code "81") (name "Net-(L28-PadA)") (class "Default")
      (node (ref "L28") (pin "A") (pinfunction "A_A") (pintype "passive"))
      (node (ref "R58") (pin "1") (pinfunction "1_1") (pintype "passive"))
    )
    (net (code "82") (name "Net-(L29-PadA)") (class "Default")
      (node (ref "L29") (pin "A") (pinfunction "A_A") (pintype "passive"))
      (node (ref "R59") (pin "1") (pinfunction "1_1") (pintype "passive"))
    )
    (net (code "83") (name "Net-(L30-PadA)") (class "Default")
      (node (ref "L30") (pin "A") (pinfunction "A_A") (pintype "passive"))
      (node (ref "R60") (pin "1") (pinfunction "1_1") (pintype "passive"))
    )
    (net (code "84") (name "Net-(L31-PadA)") (class "Default")
      (node (ref "L31") (pin "A") (pinfunction "A_A") (pintype "passive"))
      (node (ref "R65") (pin "1") (pinfunction "1_1") (pintype "passive"))
    )
    (net (code "85") (name "Net-(L32-PadA)") (class "Default")
      (node (ref "L32") (pin "A") (pinfunction "A_A") (pintype "passive"))
      (node (ref "R66") (pin "1") (pinfunction "1_1") (pintype "passive"))
    )
    (net (code "86") (name "Net-(L33-PadA)") (class "Default")
      (node (ref "L33") (pin "A") (pinfunction "A_A") (pintype "passive"))
      (node (ref "R67") (pin "1") (pinfunction "1_1") (pintype "passive"))
    )
    (net (code "87") (name "Net-(L34-PadA)") (class "Default")
      (node (ref "L34") (pin "A") (pinfunction "A_A") (pintype "passive"))
      (node (ref "R68") (pin "1") (pinfunction "1_1") (pintype "passive"))
    )
    (net (code "88") (name "Net-(L35-PadA)") (class "Default")
      (node (ref "L35") (pin "A") (pinfunction "A_A") (pintype "passive"))
      (node (ref "R69") (pin "1") (pinfunction "1_1") (pintype "passive"))
    )
    (net (code "89") (name "Net-(L36-PadA)") (class "Default")
      (node (ref "L36") (pin "A") (pinfunction "A_A") (pintype "passive"))
      (node (ref "R70") (pin "1") (pinfunction "1_1") (pintype "passive"))
    )
    (net (code "90") (name "Net-(L37-PadA)") (class "Default")
      (node (ref "L37") (pin "A") (pinfunction "A_A") (pintype "passive"))
      (node (ref "R71") (pin "1") (pinfunction "1_1") (pintype "passive"))
    )
    (net (code "91") (name "Net-(U4-BOOT0)") (class "Default")
      (node (ref "R78") (pin "2") (pinfunction "2_2") (pintype "passive"))
      (node (ref "U4") (pin "60") (pinfunction "BOOT0_60") (pintype "input"))
    )
    (net (code "92") (name "Net-(U4-PH0-OSC_IN{slash}EVENTOUT)") (class "Default")
      (node (ref "C2") (pin "1") (pinfunction "1_1") (pintype "passive"))
      (node (ref "U4") (pin "5") (pinfunction "PH0-OSC_IN/EVENTOUT_5") (pintype "bidirectional"))
      (node (ref "X2") (pin "P$2") (pinfunction "2_P$2") (pintype "passive"))
    )
    (net (code "93") (name "Net-(U4-PH1-OSC_OUT{slash}EVENTOUT)") (class "Default")
      (node (ref "C3") (pin "1") (pinfunction "1_1") (pintype "passive"))
      (node (ref "U4") (pin "6") (pinfunction "PH1-OSC_OUT/EVENTOUT_6") (pintype "bidirectional"))
      (node (ref "X2") (pin "P$1") (pinfunction "1_P$1") (pintype "passive"))
    )
    (net (code "94") (name "Net-(U4-VCAP_1)") (class "Default")
      (node (ref "C1") (pin "1") (pinfunction "1_1") (pintype "passive"))
      (node (ref "U4") (pin "30") (pinfunction "VCAP_1_30") (pintype "power_in"))
    )
    (net (code "95") (name "unconnected-(U4-PA1{slash}TIM2_CH2{slash}TIM5_CH2{slash}USART2_RTS{slash}UART4_RX{slash}QUADSPI_BK1_IO3{slash}SAI2_MCLK_B{slash}EVENTOUT-Pad15)") (class "Default")
      (node (ref "U4") (pin "15") (pinfunction "PA1/TIM2_CH2/TIM5_CH2/USART2_RTS/UART4_RX/QUADSPI_BK1_IO3/SAI2_MCLK_B/EVENTOUT_15") (pintype "bidirectional"))
    )
    (net (code "96") (name "unconnected-(U4-PA6{slash}TIM1_BKIN{slash}TIM3_CH1{slash}TIM8_BKIN{slash}SPI1_MISO{slash}I2S2_MCK{slash}TIM13_CH1{slash}DCMI_PIXCLK{slash}EVENTOUT-Pad22)") (class "Default")
      (node (ref "U4") (pin "22") (pinfunction "PA6/TIM1_BKIN/TIM3_CH1/TIM8_BKIN/SPI1_MISO/I2S2_MCK/TIM13_CH1/DCMI_PIXCLK/EVENTOUT_22") (pintype "bidirectional"))
    )
    (net (code "97") (name "unconnected-(U4-PA8{slash}MCO1{slash}TIM1_CH1{slash}I2C3_SCL{slash}USART1_CK{slash}OTG_FS_SOF{slash}EVENTOUT-Pad41)") (class "Default")
      (node (ref "U4") (pin "41") (pinfunction "PA8/MCO1/TIM1_CH1/I2C3_SCL/USART1_CK/OTG_FS_SOF/EVENTOUT_41") (pintype "bidirectional"))
    )
    (net (code "98") (name "unconnected-(U4-PA9{slash}TIM1_CH2{slash}I2C3_SMBA{slash}SPI2_SCK{slash}I2S2_CK{slash}SAI1_SD_B{slash}USART1_TX{slash}DCMI_D0{slash}EVENTOUT-Pad42)") (class "Default")
      (node (ref "U4") (pin "42") (pinfunction "PA9/TIM1_CH2/I2C3_SMBA/SPI2_SCK/I2S2_CK/SAI1_SD_B/USART1_TX/DCMI_D0/EVENTOUT_42") (pintype "bidirectional"))
    )
    (net (code "99") (name "unconnected-(U4-PA10{slash}TIM1_CH3{slash}USART1_RX{slash}OTG_FS_ID{slash}DCMI_D1{slash}EVENTOUT-Pad43)") (class "Default")
      (node (ref "U4") (pin "43") (pinfunction "PA10/TIM1_CH3/USART1_RX/OTG_FS_ID/DCMI_D1/EVENTOUT_43") (pintype "bidirectional"))
    )
    (net (code "100") (name "unconnected-(U4-PA11{slash}TIM1_CH4{slash}USART1_CTS{slash}CAN1_RX{slash}OTG_FS_DM{slash}EVENTOUT-Pad44)") (class "Default")
      (node (ref "U4") (pin "44") (pinfunction "PA11/TIM1_CH4/USART1_CTS/CAN1_RX/OTG_FS_DM/EVENTOUT_44") (pintype "bidirectional"))
    )
    (net (code "101") (name "unconnected-(U4-PA12{slash}TIM1_ETR{slash}USART1_RTS{slash}SAI2_FS_B{slash}CAN1_TX{slash}OTG_FS_DP{slash}EVENTOUT-Pad45)") (class "Default")
      (node (ref "U4") (pin "45") (pinfunction "PA12/TIM1_ETR/USART1_RTS/SAI2_FS_B/CAN1_TX/OTG_FS_DP/EVENTOUT_45") (pintype "bidirectional"))
    )
    (net (code "102") (name "unconnected-(U4-PA15{slash}JTDI{slash}TIM2_CH1{slash}TIM2_ETR{slash}HDMI_CEC{slash}SPI1_NSS{slash}I2S1_WS{slash}SPI3_NSS{slash}I2S3_WS{slash}UART4_RTS{slash}EVENTOUT-Pad50)") (class "Default")
      (node (ref "U4") (pin "50") (pinfunction "PA15/JTDI/TIM2_CH1/TIM2_ETR/HDMI_CEC/SPI1_NSS/I2S1_WS/SPI3_NSS/I2S3_WS/UART4_RTS/EVENTOUT_50") (pintype "bidirectional"))
    )
    (net (code "103") (name "unconnected-(U4-PB2-BOOT1(PB2){slash}TIM2_CH4{slash}SAI1_SD_A{slash}SPI3_MOSI{slash}I2S3_SD{slash}QUADSPI_CLK{slash}OTG_HS_ULPI_D4{slash}SDIO_CK{slash}EVENTOUT-Pad28)") (class "Default")
      (node (ref "U4") (pin "28") (pinfunction "PB2-BOOT1(PB2)/TIM2_CH4/SAI1_SD_A/SPI3_MOSI/I2S3_SD/QUADSPI_CLK/OTG_HS_ULPI_D4/SDIO_CK/EVENTOUT_28") (pintype "bidirectional"))
    )
    (net (code "104") (name "unconnected-(U4-PB3(JTDO{slash}TRACESWO){slash}JTDO{slash}TRACESWO{slash}TIM2_CH2{slash}I2C2_SDA{slash}SPI1_SCK{slash}I2S1_CK{slash}SPI3_SCK{slash}I2S3_CK{slash}EVENTOUT-Pad55)") (class "Default")
      (node (ref "U4") (pin "55") (pinfunction "PB3(JTDO/TRACESWO)/JTDO/TRACESWO/TIM2_CH2/I2C2_SDA/SPI1_SCK/I2S1_CK/SPI3_SCK/I2S3_CK/EVENTOUT_55") (pintype "bidirectional"))
    )
    (net (code "105") (name "unconnected-(U4-PB4(NJTRST){slash}NJTRST{slash}TIM3_CH1{slash}I2C3_SDA{slash}SPI1_MISO{slash}SPI3_MISO{slash}SPI2_NSS{slash}I2S2_WS{slash}EVENTOUT-Pad56)") (class "Default")
      (node (ref "U4") (pin "56") (pinfunction "PB4(NJTRST)/NJTRST/TIM3_CH1/I2C3_SDA/SPI1_MISO/SPI3_MISO/SPI2_NSS/I2S2_WS/EVENTOUT_56") (pintype "bidirectional"))
    )
    (net (code "106") (name "unconnected-(U4-PB5{slash}TIM3_CH2{slash}I2C1_SMBA{slash}SPI1_MOSI{slash}I2S1_SD{slash}SPI3_MOSI{slash}I2S3_SD{slash}CAN2_RX{slash}OTG_HS_ULPI_D7{slash}FMC_SDCKE1{slash}DCMI_D10{slash}EVENTOUT-Pad57)") (class "Default")
      (node (ref "U4") (pin "57") (pinfunction "PB5/TIM3_CH2/I2C1_SMBA/SPI1_MOSI/I2S1_SD/SPI3_MOSI/I2S3_SD/CAN2_RX/OTG_HS_ULPI_D7/FMC_SDCKE1/DCMI_D10/EVENTOUT_57") (pintype "bidirectional"))
    )
    (net (code "107") (name "unconnected-(U4-PB6{slash}TIM4_CH1{slash}HDMI_CEC{slash}I2C1_SCL{slash}USART1_TX{slash}CAN2_TX{slash}QUADSPI_BK1_NCS{slash}FMC_SDNE1{slash}DCMI_D5{slash}EVENTOUT-Pad58)") (class "Default")
      (node (ref "U4") (pin "58") (pinfunction "PB6/TIM4_CH1/HDMI_CEC/I2C1_SCL/USART1_TX/CAN2_TX/QUADSPI_BK1_NCS/FMC_SDNE1/DCMI_D5/EVENTOUT_58") (pintype "bidirectional"))
    )
    (net (code "108") (name "unconnected-(U4-PB8{slash}TIM2_CH1{slash}TIM2_ETR{slash}TIM4_CH3{slash}TIM10_CH1{slash}I2C1_SCL{slash}CAN1_RX{slash}SDIO_D4{slash}DCMI_D6{slash}EVENTOUT-Pad61)") (class "Default")
      (node (ref "U4") (pin "61") (pinfunction "PB8/TIM2_CH1/TIM2_ETR/TIM4_CH3/TIM10_CH1/I2C1_SCL/CAN1_RX/SDIO_D4/DCMI_D6/EVENTOUT_61") (pintype "bidirectional"))
    )
    (net (code "109") (name "unconnected-(U4-PB10{slash}TIM2_CH3{slash}I2C2_SCL{slash}SPI2_SCK{slash}I2S2_CK{slash}SAI1_SCK_A{slash}USART3_TX{slash}OTG_HS_ULPI_D3{slash}EVENTOUT-Pad29)") (class "Default")
      (node (ref "U4") (pin "29") (pinfunction "PB10/TIM2_CH3/I2C2_SCL/SPI2_SCK/I2S2_CK/SAI1_SCK_A/USART3_TX/OTG_HS_ULPI_D3/EVENTOUT_29") (pintype "bidirectional"))
    )
    (net (code "110") (name "unconnected-(U4-PB14{slash}TIM1_CH2N{slash}TIM8_CH2N{slash}SPI2_MISO{slash}USART3_RTS{slash}TIM12_CH1{slash}OTG_HS_DM{slash}EVENTOUT-Pad35)") (class "Default")
      (node (ref "U4") (pin "35") (pinfunction "PB14/TIM1_CH2N/TIM8_CH2N/SPI2_MISO/USART3_RTS/TIM12_CH1/OTG_HS_DM/EVENTOUT_35") (pintype "bidirectional"))
    )
    (net (code "111") (name "unconnected-(U4-PB15{slash}RTC_REFIN{slash}TIM1_CH3N{slash}TIM8_CH3N{slash}SPI2_MOSI{slash}I2S2_SD{slash}TIM12_CH2{slash}OTG_HS_DP{slash}EVENTOUT-Pad36)") (class "Default")
      (node (ref "U4") (pin "36") (pinfunction "PB15/RTC_REFIN/TIM1_CH3N/TIM8_CH3N/SPI2_MOSI/I2S2_SD/TIM12_CH2/OTG_HS_DP/EVENTOUT_36") (pintype "bidirectional"))
    )
    (net (code "112") (name "unconnected-(U4-PC8{slash}TRACED0{slash}TIM3_CH3{slash}TIM8_CH3{slash}UART5_RTS{slash}USART6_CK{slash}SDIO_D0{slash}DCMI_D2{slash}EVENTOUT-Pad39)") (class "Default")
      (node (ref "U4") (pin "39") (pinfunction "PC8/TRACED0/TIM3_CH3/TIM8_CH3/UART5_RTS/USART6_CK/SDIO_D0/DCMI_D2/EVENTOUT_39") (pintype "bidirectional"))
    )
    (net (code "113") (name "unconnected-(U4-PC9{slash}MCO2{slash}TIM3_CH4{slash}TIM8_CH4{slash}I2C3_SDA{slash}I2S_CKIN{slash}UART5_CTS{slash}QUADSPI_BK1_IO0{slash}SDIO_D1{slash}DCMI_D3{slash}EVENTOUT-Pad40)") (class "Default")
      (node (ref "U4") (pin "40") (pinfunction "PC9/MCO2/TIM3_CH4/TIM8_CH4/I2C3_SDA/I2S_CKIN/UART5_CTS/QUADSPI_BK1_IO0/SDIO_D1/DCMI_D3/EVENTOUT_40") (pintype "bidirectional"))
    )
    (net (code "114") (name "unconnected-(U4-PC13{slash}EVENTOUT-Pad2)") (class "Default")
      (node (ref "U4") (pin "2") (pinfunction "PC13/EVENTOUT_2") (pintype "bidirectional"))
    )
    (net (code "115") (name "unconnected-(U4-PC14-OSC32_IN(PC14){slash}EVENTOUT-Pad3)") (class "Default")
      (node (ref "U4") (pin "3") (pinfunction "PC14-OSC32_IN(PC14)/EVENTOUT_3") (pintype "bidirectional"))
    )
    (net (code "116") (name "unconnected-(U4-PC15-OSC32_OUT(PC15){slash}EVENTOUT-Pad4)") (class "Default")
      (node (ref "U4") (pin "4") (pinfunction "PC15-OSC32_OUT(PC15)/EVENTOUT_4") (pintype "bidirectional"))
    )
    (net (code "117") (name "unconnected-(U4-PD2{slash}TIM3_ETR{slash}UART5_RX{slash}SDIO_CMD{slash}DCMI_D11{slash}EVENTOUT-Pad54)") (class "Default")
      (node (ref "U4") (pin "54") (pinfunction "PD2/TIM3_ETR/UART5_RX/SDIO_CMD/DCMI_D11/EVENTOUT_54") (pintype "bidirectional"))
    )
  )
)
